# E-22_Blaster_Bit.net
KiCad netlist of a schematic drawn in Altium Designer
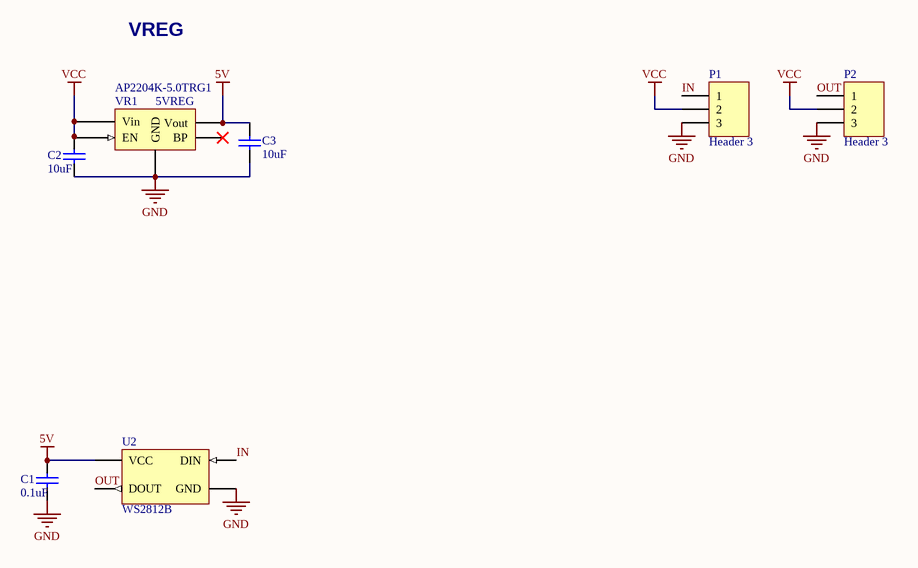
[diagram p0: E-22 Blaster Bit.SchDoc]

(export (version "E")
  (design (tool "Eeschema 10.0.6"))
  (components
    (comp (ref "C1")
      (value "0.1uF")
      (footprint "0805 TIGHT")
      (description "Capacitor")
      (fields (field (name "Comment") "18pF") (field (name "PUBLISHER") "Altium Limited"))
      (libsource (lib "SB_Discrete") (part "Cap"))
    )
    (comp (ref "C2")
      (value "10uF")
      (footprint "0805 TIGHT")
      (description "Capacitor")
      (fields (field (name "Comment") "2.2uF") (field (name "PUBLISHER") "Altium Limited"))
      (libsource (lib "SB_Discrete") (part "Cap"))
    )
    (comp (ref "C3")
      (value "10uF")
      (footprint "0805 TIGHT")
      (description "Capacitor")
      (fields (field (name "Comment") "100nF") (field (name "PUBLISHER") "Altium Limited"))
      (libsource (lib "SB_Discrete") (part "Cap"))
    )
    (comp (ref "P1")
      (value "Header 3")
      (footprint "JST-PH 3-PIN")
      (description "Header, 3-Pin")
      (fields (field (name "PUBLISHER") "Altium Limited"))
      (libsource (lib "Miscellaneous Connectors") (part "Header 3"))
    )
    (comp (ref "P2")
      (value "Header 3")
      (footprint "HDR1X3")
      (description "Header, 3-Pin")
      (fields (field (name "PUBLISHER") "Altium Limited"))
      (libsource (lib "Miscellaneous Connectors") (part "Header 3"))
    )
    (comp (ref "U2")
      (value "WS2812B")
      (footprint "ws2812b")
      (libsource (lib "SB_Engineered_Components") (part "WS2812B"))
    )
    (comp (ref "VR1")
      (value "5VREG")
      (footprint "SOT-25 New")
      (libsource (lib "SB_Discrete") (part "Vreg SOT25"))
    )
  )
  (nets
    (net (code "2") (name "/IN") (class "Default")
      (node (ref "P1") (pin "1") (pinfunction "1_1") (pintype "passive"))
      (node (ref "U2") (pin "4") (pinfunction "DIN_4") (pintype "input"))
    )
    (net (code "3") (name "/OUT") (class "Default")
      (node (ref "P2") (pin "1") (pinfunction "1_1") (pintype "passive"))
      (node (ref "U2") (pin "2") (pinfunction "DOUT_2") (pintype "output"))
    )
    (net (code "4") (name "5V") (class "Default")
      (node (ref "C1") (pin "2") (pinfunction "2_2") (pintype "passive"))
      (node (ref "C3") (pin "1") (pinfunction "1_1") (pintype "passive"))
      (node (ref "U2") (pin "1") (pinfunction "VCC_1") (pintype "power_in"))
      (node (ref "VR1") (pin "2") (pinfunction "Vout_2") (pintype "passive"))
    )
    (net (code "5") (name "GND") (class "Default")
      (node (ref "C1") (pin "1") (pinfunction "1_1") (pintype "passive"))
      (node (ref "C2") (pin "2") (pinfunction "2_2") (pintype "passive"))
      (node (ref "C3") (pin "2") (pinfunction "2_2") (pintype "passive"))
      (node (ref "P1") (pin "3") (pinfunction "3_3") (pintype "passive"))
      (node (ref "P2") (pin "3") (pinfunction "3_3") (pintype "passive"))
      (node (ref "U2") (pin "3") (pinfunction "GND_3") (pintype "power_in"))
      (node (ref "VR1") (pin "3") (pinfunction "GND_3") (pintype "passive"))
    )
    (net (code "6") (name "VCC") (class "Default")
      (node (ref "C2") (pin "1") (pinfunction "1_1") (pintype "passive"))
      (node (ref "P1") (pin "2") (pinfunction "2_2") (pintype "passive"))
      (node (ref "P2") (pin "2") (pinfunction "2_2") (pintype "passive"))
      (node (ref "VR1") (pin "4") (pinfunction "EN_4") (pintype "input"))
      (node (ref "VR1") (pin "5") (pinfunction "Vin_5") (pintype "passive"))
    )
    (net (code "7") (name "unconnected-(VR1-BP-Pad1)") (class "Default")
      (node (ref "VR1") (pin "1") (pinfunction "BP_1") (pintype "passive+no_connect"))
    )
  )
)
